# PersiBT.net
KiCad netlist of a schematic drawn in EAGLE
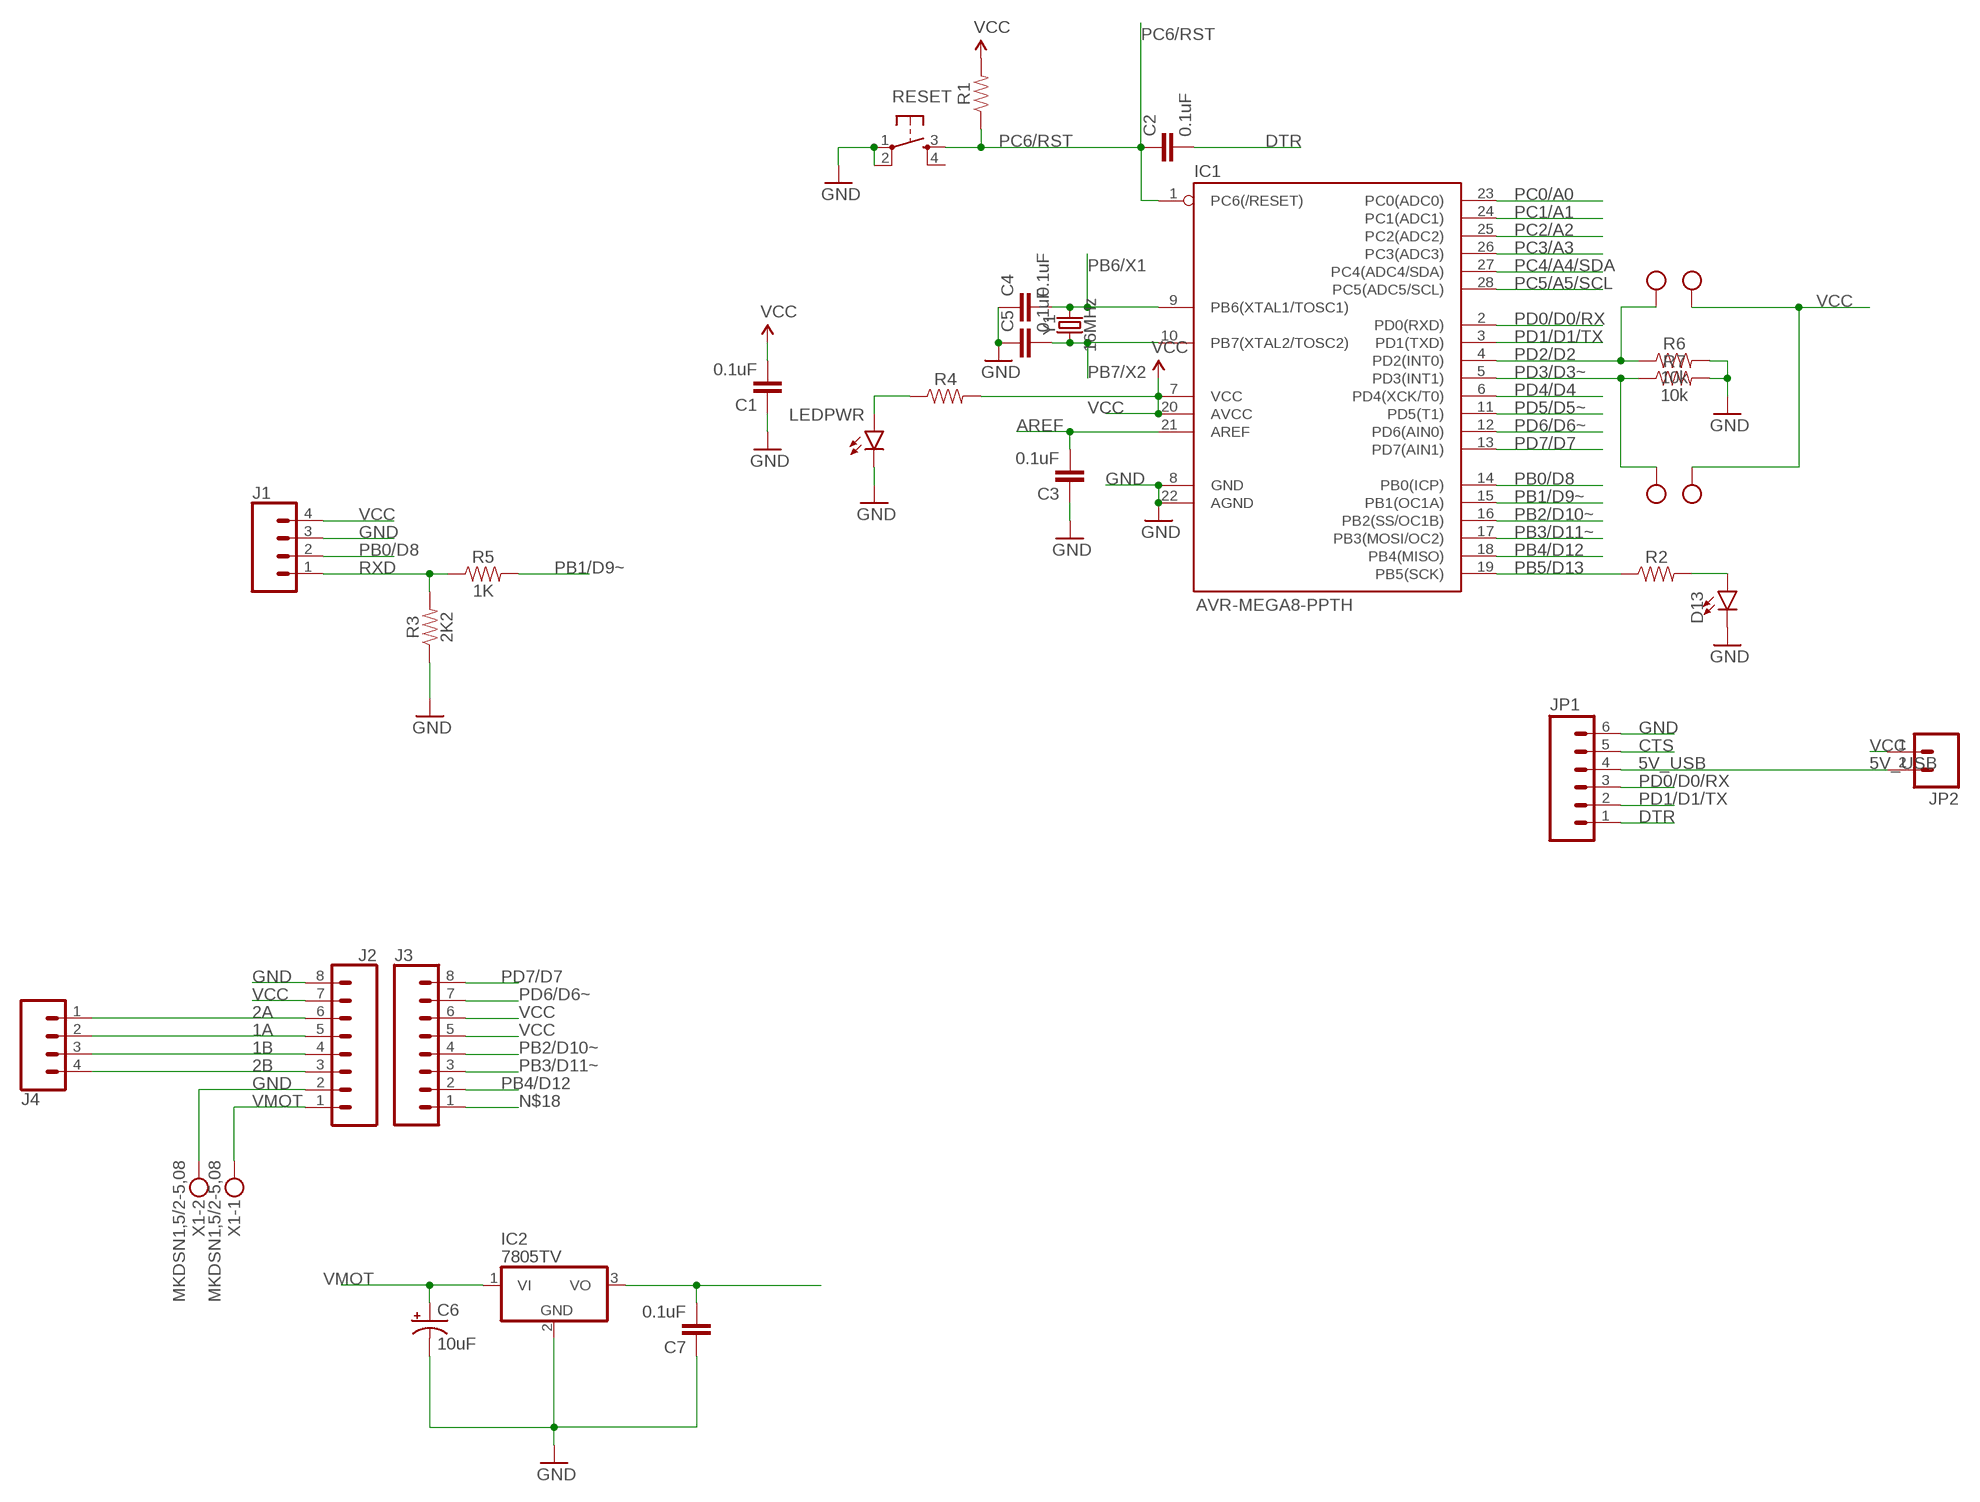
[diagram p0: schematic, sheet 1]

(export (version "E")
  (design (tool "Eeschema 10.0.6"))
  (components
    (comp (ref "C1")
      (value "0.1uF")
      (footprint "eagle-import:CAP-PTH-SMALL-KIT")
      (libsource (lib "eagle-import") (part "0.1UF-KIT-EZ-50V-20%"))
    )
    (comp (ref "C2")
      (value "0.1uF")
      (footprint "eagle-import:CAP-PTH-SMALL-KIT")
      (libsource (lib "eagle-import") (part "0.1UF-KIT-EZ-50V-20%"))
    )
    (comp (ref "C3")
      (value "0.1uF")
      (footprint "eagle-import:CAP-PTH-SMALL-KIT")
      (libsource (lib "eagle-import") (part "0.1UF-KIT-EZ-50V-20%"))
    )
    (comp (ref "C4")
      (value "0.1uF")
      (footprint "eagle-import:CAP-PTH-SMALL-KIT")
      (libsource (lib "eagle-import") (part "0.1UF-KIT-EZ-50V-20%"))
    )
    (comp (ref "C5")
      (value "0.1uF")
      (footprint "eagle-import:CAP-PTH-SMALL-KIT")
      (libsource (lib "eagle-import") (part "0.1UF-KIT-EZ-50V-20%"))
    )
    (comp (ref "C6")
      (value "10uF")
      (footprint "eagle-import:CPOL-RADIAL-2.5MM-5MM-KIT")
      (libsource (lib "eagle-import") (part "10UF-POLAR-RADIAL-2.5MM-KIT-25V-20%"))
    )
    (comp (ref "C7")
      (value "0.1uF")
      (footprint "eagle-import:CAP-PTH-SMALL-KIT")
      (libsource (lib "eagle-import") (part "0.1UF-KIT-EZ-50V-20%"))
    )
    (comp (ref "D13")
      (value "LED5MM-KIT")
      (footprint "eagle-import:LED_5MM-KIT")
      (libsource (lib "eagle-import") (part "LED5MM-KIT"))
    )
    (comp (ref "IC1")
      (value "AVR-MEGA8-PPTH")
      (footprint "eagle-import:DIL28-3")
      (libsource (lib "eagle-import") (part "AVR-MEGA8-PPTH"))
    )
    (comp (ref "IC2")
      (value "7805TV")
      (footprint "eagle-import:TO220V")
      (libsource (lib "eagle-import") (part "78TV05"))
    )
    (comp (ref "J1")
      (value "CONN_04")
      (footprint "eagle-import:1X04")
      (libsource (lib "eagle-import") (part "CONN_04"))
    )
    (comp (ref "J2")
      (value "CONN_08\"")
      (footprint "eagle-import:1X08")
      (libsource (lib "eagle-import") (part "CONN_08{dblquote}"))
    )
    (comp (ref "J3")
      (value "CONN_08\"")
      (footprint "eagle-import:1X08")
      (libsource (lib "eagle-import") (part "CONN_08{dblquote}"))
    )
    (comp (ref "J4")
      (value "CONN_04")
      (footprint "eagle-import:1X04")
      (libsource (lib "eagle-import") (part "CONN_04"))
    )
    (comp (ref "JP1")
      (value "M06SIP")
      (footprint "eagle-import:1X06")
      (libsource (lib "eagle-import") (part "M06SIP"))
    )
    (comp (ref "JP2")
      (value "M02PTH")
      (footprint "eagle-import:1X02")
      (libsource (lib "eagle-import") (part "M02PTH"))
    )
    (comp (ref "LEDPWR")
      (value "LED5MM-KIT")
      (footprint "eagle-import:LED_5MM-KIT")
      (libsource (lib "eagle-import") (part "LED5MM-KIT"))
    )
    (comp (ref "R1")
      (value "RESISTORAXIAL-0.3-KIT")
      (footprint "eagle-import:AXIAL-0.3-KIT")
      (libsource (lib "eagle-import") (part "RESISTORAXIAL-0.3-KIT"))
    )
    (comp (ref "R2")
      (value "RESISTORAXIAL-0.3-KIT")
      (footprint "eagle-import:AXIAL-0.3-KIT")
      (libsource (lib "eagle-import") (part "RESISTORAXIAL-0.3-KIT"))
    )
    (comp (ref "R3")
      (value "2K2")
      (footprint "eagle-import:AXIAL-0.3-KIT")
      (libsource (lib "eagle-import") (part "RESISTORAXIAL-0.3-KIT"))
    )
    (comp (ref "R4")
      (value "RESISTORAXIAL-0.3-KIT")
      (footprint "eagle-import:AXIAL-0.3-KIT")
      (libsource (lib "eagle-import") (part "RESISTORAXIAL-0.3-KIT"))
    )
    (comp (ref "R5")
      (value "1K")
      (footprint "eagle-import:AXIAL-0.3-KIT")
      (libsource (lib "eagle-import") (part "RESISTORAXIAL-0.3-KIT"))
    )
    (comp (ref "R6")
      (value "10k")
      (footprint "eagle-import:AXIAL-0.3-KIT")
      (libsource (lib "eagle-import") (part "RESISTORAXIAL-0.3-KIT"))
    )
    (comp (ref "R7")
      (value "10k")
      (footprint "eagle-import:AXIAL-0.3-KIT")
      (libsource (lib "eagle-import") (part "RESISTORAXIAL-0.3-KIT"))
    )
    (comp (ref "RESET")
      (value "TAC_SWITCHPTH")
      (footprint "eagle-import:TACTILE-PTH")
      (libsource (lib "eagle-import") (part "TAC_SWITCHPTH"))
    )
    (comp (ref "X1")
      (value "MKDSN1,5/2-5,08")
      (footprint "eagle-import:MKDSN1,5_2-5,08")
      (libsource (lib "eagle-import") (part "MKDSN1,5/2-5,08"))
    )
    (comp (ref "X2")
      (value "MKDSN1,5/2-5,08")
      (footprint "eagle-import:MKDSN1,5_2-5,08")
      (libsource (lib "eagle-import") (part "MKDSN1,5/2-5,08"))
    )
    (comp (ref "X3")
      (value "MKDSN1,5/2-5,08")
      (footprint "eagle-import:MKDSN1,5_2-5,08")
      (libsource (lib "eagle-import") (part "MKDSN1,5/2-5,08"))
    )
    (comp (ref "Y1")
      (value "16MHz")
      (footprint "eagle-import:HC49US")
      (libsource (lib "eagle-import") (part "CRYSTAL-16MHZPTH-HC49US"))
    )
  )
  (nets
    (net (code "1") (name "/1A") (class "Default")
      (node (ref "J2") (pin "5") (pinfunction "5_5") (pintype "passive"))
      (node (ref "J4") (pin "2") (pinfunction "2_2") (pintype "passive"))
    )
    (net (code "2") (name "/1B") (class "Default")
      (node (ref "J2") (pin "4") (pinfunction "4_4") (pintype "passive"))
      (node (ref "J4") (pin "3") (pinfunction "3_3") (pintype "passive"))
    )
    (net (code "3") (name "/2A") (class "Default")
      (node (ref "J2") (pin "6") (pinfunction "6_6") (pintype "passive"))
      (node (ref "J4") (pin "1") (pinfunction "1_1") (pintype "passive"))
    )
    (net (code "4") (name "/2B") (class "Default")
      (node (ref "J2") (pin "3") (pinfunction "3_3") (pintype "passive"))
      (node (ref "J4") (pin "4") (pinfunction "4_4") (pintype "passive"))
    )
    (net (code "5") (name "/5V_USB") (class "Default")
      (node (ref "JP1") (pin "4") (pinfunction "4_4") (pintype "passive"))
      (node (ref "JP2") (pin "2") (pinfunction "2_2") (pintype "passive"))
    )
    (net (code "6") (name "/AREF") (class "Default")
      (node (ref "C3") (pin "2") (pinfunction "2_2") (pintype "passive"))
      (node (ref "IC1") (pin "21") (pinfunction "AREF_21") (pintype "bidirectional"))
    )
    (net (code "7") (name "/CTS") (class "Default")
      (node (ref "JP1") (pin "5") (pinfunction "5_5") (pintype "passive"))
    )
    (net (code "8") (name "/DTR") (class "Default")
      (node (ref "C2") (pin "2") (pinfunction "2_2") (pintype "passive"))
      (node (ref "JP1") (pin "1") (pinfunction "1_1") (pintype "passive"))
    )
    (net (code "9") (name "/N$18") (class "Default")
      (node (ref "J3") (pin "1") (pinfunction "1_1") (pintype "passive"))
    )
    (net (code "10") (name "/PB0{slash}D8") (class "Default")
      (node (ref "IC1") (pin "14") (pinfunction "PB0(ICP)_14") (pintype "bidirectional"))
      (node (ref "J1") (pin "2") (pinfunction "2_2") (pintype "passive"))
    )
    (net (code "11") (name "/PB1{slash}D9~{}") (class "Default")
      (node (ref "IC1") (pin "15") (pinfunction "PB1(OC1A)_15") (pintype "bidirectional"))
      (node (ref "R5") (pin "P$2") (pinfunction "2_P$2") (pintype "passive"))
    )
    (net (code "12") (name "/PB2{slash}D10~{}") (class "Default")
      (node (ref "IC1") (pin "16") (pinfunction "PB2(SS/OC1B)_16") (pintype "bidirectional"))
      (node (ref "J3") (pin "4") (pinfunction "4_4") (pintype "passive"))
    )
    (net (code "13") (name "/PB3{slash}D11~{}") (class "Default")
      (node (ref "IC1") (pin "17") (pinfunction "PB3(MOSI/OC2)_17") (pintype "bidirectional"))
      (node (ref "J3") (pin "3") (pinfunction "3_3") (pintype "passive"))
    )
    (net (code "14") (name "/PB4{slash}D12") (class "Default")
      (node (ref "IC1") (pin "18") (pinfunction "PB4(MISO)_18") (pintype "bidirectional"))
      (node (ref "J3") (pin "2") (pinfunction "2_2") (pintype "passive"))
    )
    (net (code "15") (name "/PB5{slash}D13") (class "Default")
      (node (ref "IC1") (pin "19") (pinfunction "PB5(SCK)_19") (pintype "bidirectional"))
      (node (ref "R2") (pin "P$1") (pinfunction "1_P$1") (pintype "passive"))
    )
    (net (code "16") (name "/PB6{slash}X1") (class "Default")
      (node (ref "C4") (pin "2") (pinfunction "2_2") (pintype "passive"))
      (node (ref "IC1") (pin "9") (pinfunction "PB6(XTAL1/TOSC1)_9") (pintype "bidirectional"))
      (node (ref "Y1") (pin "2") (pinfunction "2_2") (pintype "passive"))
    )
    (net (code "17") (name "/PB7{slash}X2") (class "Default")
      (node (ref "C5") (pin "2") (pinfunction "2_2") (pintype "passive"))
      (node (ref "IC1") (pin "10") (pinfunction "PB7(XTAL2/TOSC2)_10") (pintype "bidirectional"))
      (node (ref "Y1") (pin "1") (pinfunction "1_1") (pintype "passive"))
    )
    (net (code "18") (name "/PC0{slash}A0") (class "Default")
      (node (ref "IC1") (pin "23") (pinfunction "PC0(ADC0)_23") (pintype "bidirectional"))
    )
    (net (code "19") (name "/PC1{slash}A1") (class "Default")
      (node (ref "IC1") (pin "24") (pinfunction "PC1(ADC1)_24") (pintype "bidirectional"))
    )
    (net (code "20") (name "/PC2{slash}A2") (class "Default")
      (node (ref "IC1") (pin "25") (pinfunction "PC2(ADC2)_25") (pintype "bidirectional"))
    )
    (net (code "21") (name "/PC3{slash}A3") (class "Default")
      (node (ref "IC1") (pin "26") (pinfunction "PC3(ADC3)_26") (pintype "bidirectional"))
    )
    (net (code "22") (name "/PC4{slash}A4{slash}SDA") (class "Default")
      (node (ref "IC1") (pin "27") (pinfunction "PC4(ADC4/SDA)_27") (pintype "bidirectional"))
    )
    (net (code "23") (name "/PC5{slash}A5{slash}SCL") (class "Default")
      (node (ref "IC1") (pin "28") (pinfunction "PC5(ADC5/SCL)_28") (pintype "bidirectional"))
    )
    (net (code "24") (name "/PC6{slash}RST") (class "Default")
      (node (ref "C2") (pin "1") (pinfunction "1_1") (pintype "passive"))
      (node (ref "IC1") (pin "1") (pinfunction "PC6(/RESET)_1") (pintype "bidirectional"))
      (node (ref "R1") (pin "P$1") (pinfunction "1_P$1") (pintype "passive"))
      (node (ref "RESET") (pin "3") (pinfunction "3_3") (pintype "passive"))
    )
    (net (code "25") (name "/PD0{slash}D0{slash}RX") (class "Default")
      (node (ref "IC1") (pin "2") (pinfunction "PD0(RXD)_2") (pintype "bidirectional"))
      (node (ref "JP1") (pin "3") (pinfunction "3_3") (pintype "passive"))
    )
    (net (code "26") (name "/PD1{slash}D1{slash}TX") (class "Default")
      (node (ref "IC1") (pin "3") (pinfunction "PD1(TXD)_3") (pintype "bidirectional"))
      (node (ref "JP1") (pin "2") (pinfunction "2_2") (pintype "passive"))
    )
    (net (code "27") (name "/PD2{slash}D2") (class "Default")
      (node (ref "IC1") (pin "4") (pinfunction "PD2(INT0)_4") (pintype "bidirectional"))
      (node (ref "R6") (pin "P$1") (pinfunction "1_P$1") (pintype "passive"))
      (node (ref "X2") (pin "1") (pinfunction "KL_1") (pintype "passive"))
    )
    (net (code "28") (name "/PD3{slash}D3~{}") (class "Default")
      (node (ref "IC1") (pin "5") (pinfunction "PD3(INT1)_5") (pintype "bidirectional"))
      (node (ref "R7") (pin "P$1") (pinfunction "1_P$1") (pintype "passive"))
      (node (ref "X3") (pin "2") (pinfunction "KL_2") (pintype "passive"))
    )
    (net (code "29") (name "/PD4{slash}D4") (class "Default")
      (node (ref "IC1") (pin "6") (pinfunction "PD4(XCK/T0)_6") (pintype "bidirectional"))
    )
    (net (code "30") (name "/PD5{slash}D5~{}") (class "Default")
      (node (ref "IC1") (pin "11") (pinfunction "PD5(T1)_11") (pintype "bidirectional"))
    )
    (net (code "31") (name "/PD6{slash}D6~{}") (class "Default")
      (node (ref "IC1") (pin "12") (pinfunction "PD6(AIN0)_12") (pintype "bidirectional"))
      (node (ref "J3") (pin "7") (pinfunction "7_7") (pintype "passive"))
    )
    (net (code "32") (name "/PD7{slash}D7") (class "Default")
      (node (ref "IC1") (pin "13") (pinfunction "PD7(AIN1)_13") (pintype "bidirectional"))
      (node (ref "J3") (pin "8") (pinfunction "8_8") (pintype "passive"))
    )
    (net (code "33") (name "/RXD") (class "Default")
      (node (ref "J1") (pin "1") (pinfunction "1_1") (pintype "passive"))
      (node (ref "R3") (pin "P$2") (pinfunction "2_P$2") (pintype "passive"))
      (node (ref "R5") (pin "P$1") (pinfunction "1_P$1") (pintype "passive"))
    )
    (net (code "34") (name "/VMOT") (class "Default")
      (node (ref "C6") (pin "1") (pinfunction "+_1") (pintype "passive"))
      (node (ref "IC2") (pin "1") (pinfunction "VI_1") (pintype "input"))
      (node (ref "J2") (pin "1") (pinfunction "1_1") (pintype "passive"))
      (node (ref "X1") (pin "1") (pinfunction "KL_1") (pintype "passive"))
    )
    (net (code "35") (name "GND") (class "Default")
      (node (ref "C1") (pin "1") (pinfunction "1_1") (pintype "passive"))
      (node (ref "C3") (pin "1") (pinfunction "1_1") (pintype "passive"))
      (node (ref "C4") (pin "1") (pinfunction "1_1") (pintype "passive"))
      (node (ref "C5") (pin "1") (pinfunction "1_1") (pintype "passive"))
      (node (ref "C6") (pin "2") (pinfunction "-_2") (pintype "passive"))
      (node (ref "C7") (pin "1") (pinfunction "1_1") (pintype "passive"))
      (node (ref "D13") (pin "K") (pinfunction "C_K") (pintype "passive"))
      (node (ref "IC1") (pin "22") (pinfunction "AGND_22") (pintype "bidirectional"))
      (node (ref "IC1") (pin "8") (pinfunction "GND_8") (pintype "bidirectional"))
      (node (ref "IC2") (pin "2") (pinfunction "GND_2") (pintype "passive"))
      (node (ref "J1") (pin "3") (pinfunction "3_3") (pintype "passive"))
      (node (ref "J2") (pin "2") (pinfunction "2_2") (pintype "passive"))
      (node (ref "J2") (pin "8") (pinfunction "8_8") (pintype "passive"))
      (node (ref "JP1") (pin "6") (pinfunction "6_6") (pintype "passive"))
      (node (ref "LEDPWR") (pin "K") (pinfunction "C_K") (pintype "passive"))
      (node (ref "R3") (pin "P$1") (pinfunction "1_P$1") (pintype "passive"))
      (node (ref "R6") (pin "P$2") (pinfunction "2_P$2") (pintype "passive"))
      (node (ref "R7") (pin "P$2") (pinfunction "2_P$2") (pintype "passive"))
      (node (ref "RESET") (pin "1") (pinfunction "1_1") (pintype "passive"))
      (node (ref "RESET") (pin "2") (pinfunction "2_2") (pintype "passive"))
      (node (ref "X1") (pin "2") (pinfunction "KL_2") (pintype "passive"))
    )
    (net (code "36") (name "Net-(R2-2)") (class "Default")
      (node (ref "D13") (pin "A") (pinfunction "A_A") (pintype "passive"))
      (node (ref "R2") (pin "P$2") (pinfunction "2_P$2") (pintype "passive"))
    )
    (net (code "37") (name "Net-(R4-1)") (class "Default")
      (node (ref "LEDPWR") (pin "A") (pinfunction "A_A") (pintype "passive"))
      (node (ref "R4") (pin "P$1") (pinfunction "1_P$1") (pintype "passive"))
    )
    (net (code "38") (name "VCC") (class "Default")
      (node (ref "C1") (pin "2") (pinfunction "2_2") (pintype "passive"))
      (node (ref "C7") (pin "2") (pinfunction "2_2") (pintype "passive"))
      (node (ref "IC1") (pin "20") (pinfunction "AVCC_20") (pintype "bidirectional"))
      (node (ref "IC1") (pin "7") (pinfunction "VCC_7") (pintype "bidirectional"))
      (node (ref "IC2") (pin "3") (pinfunction "VO_3") (pintype "passive"))
      (node (ref "J1") (pin "4") (pinfunction "4_4") (pintype "passive"))
      (node (ref "J2") (pin "7") (pinfunction "7_7") (pintype "passive"))
      (node (ref "J3") (pin "5") (pinfunction "5_5") (pintype "passive"))
      (node (ref "J3") (pin "6") (pinfunction "6_6") (pintype "passive"))
      (node (ref "JP2") (pin "1") (pinfunction "1_1") (pintype "passive"))
      (node (ref "R1") (pin "P$2") (pinfunction "2_P$2") (pintype "passive"))
      (node (ref "R4") (pin "P$2") (pinfunction "2_P$2") (pintype "passive"))
      (node (ref "X2") (pin "2") (pinfunction "KL_2") (pintype "passive"))
      (node (ref "X3") (pin "1") (pinfunction "KL_1") (pintype "passive"))
    )
    (net (code "39") (name "unconnected-(RESET-Pad4)") (class "Default")
      (node (ref "RESET") (pin "4") (pinfunction "4_4") (pintype "passive"))
    )
  )
)
